# SCH_StairLights_2024-01-15.net
KiCad netlist of a schematic drawn in EasyEDA
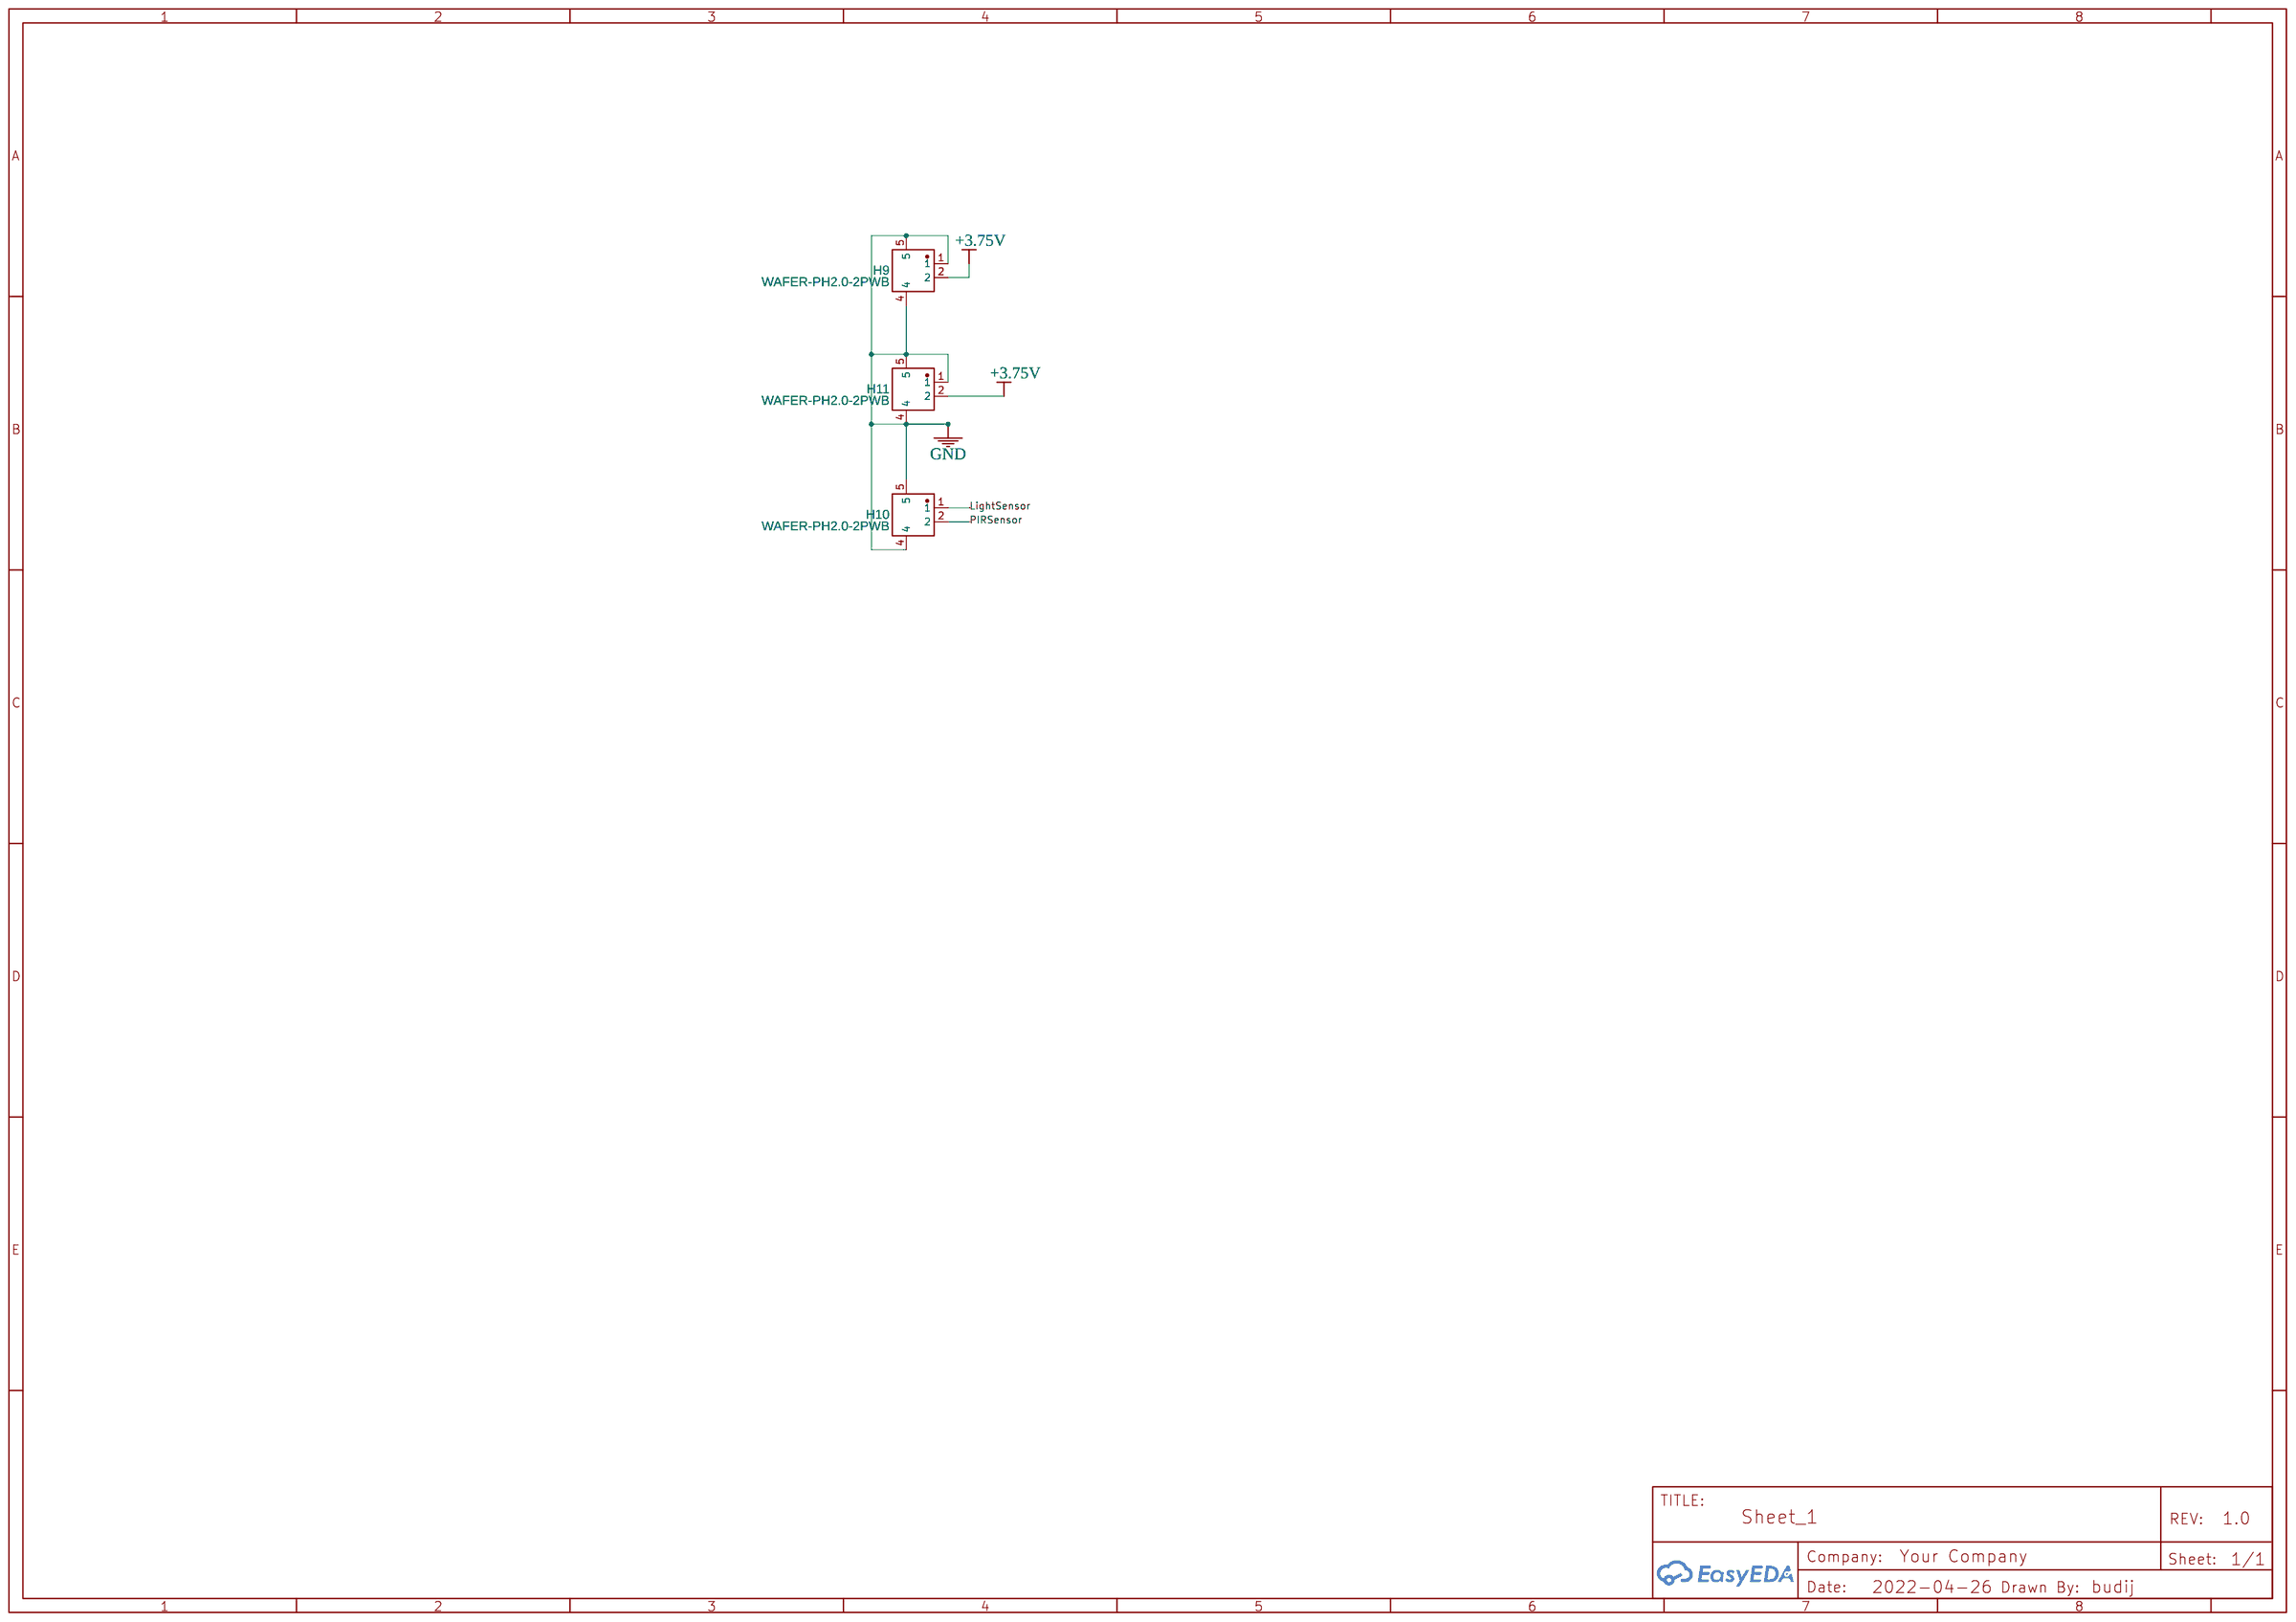
[diagram p0: StairLightsDigital]
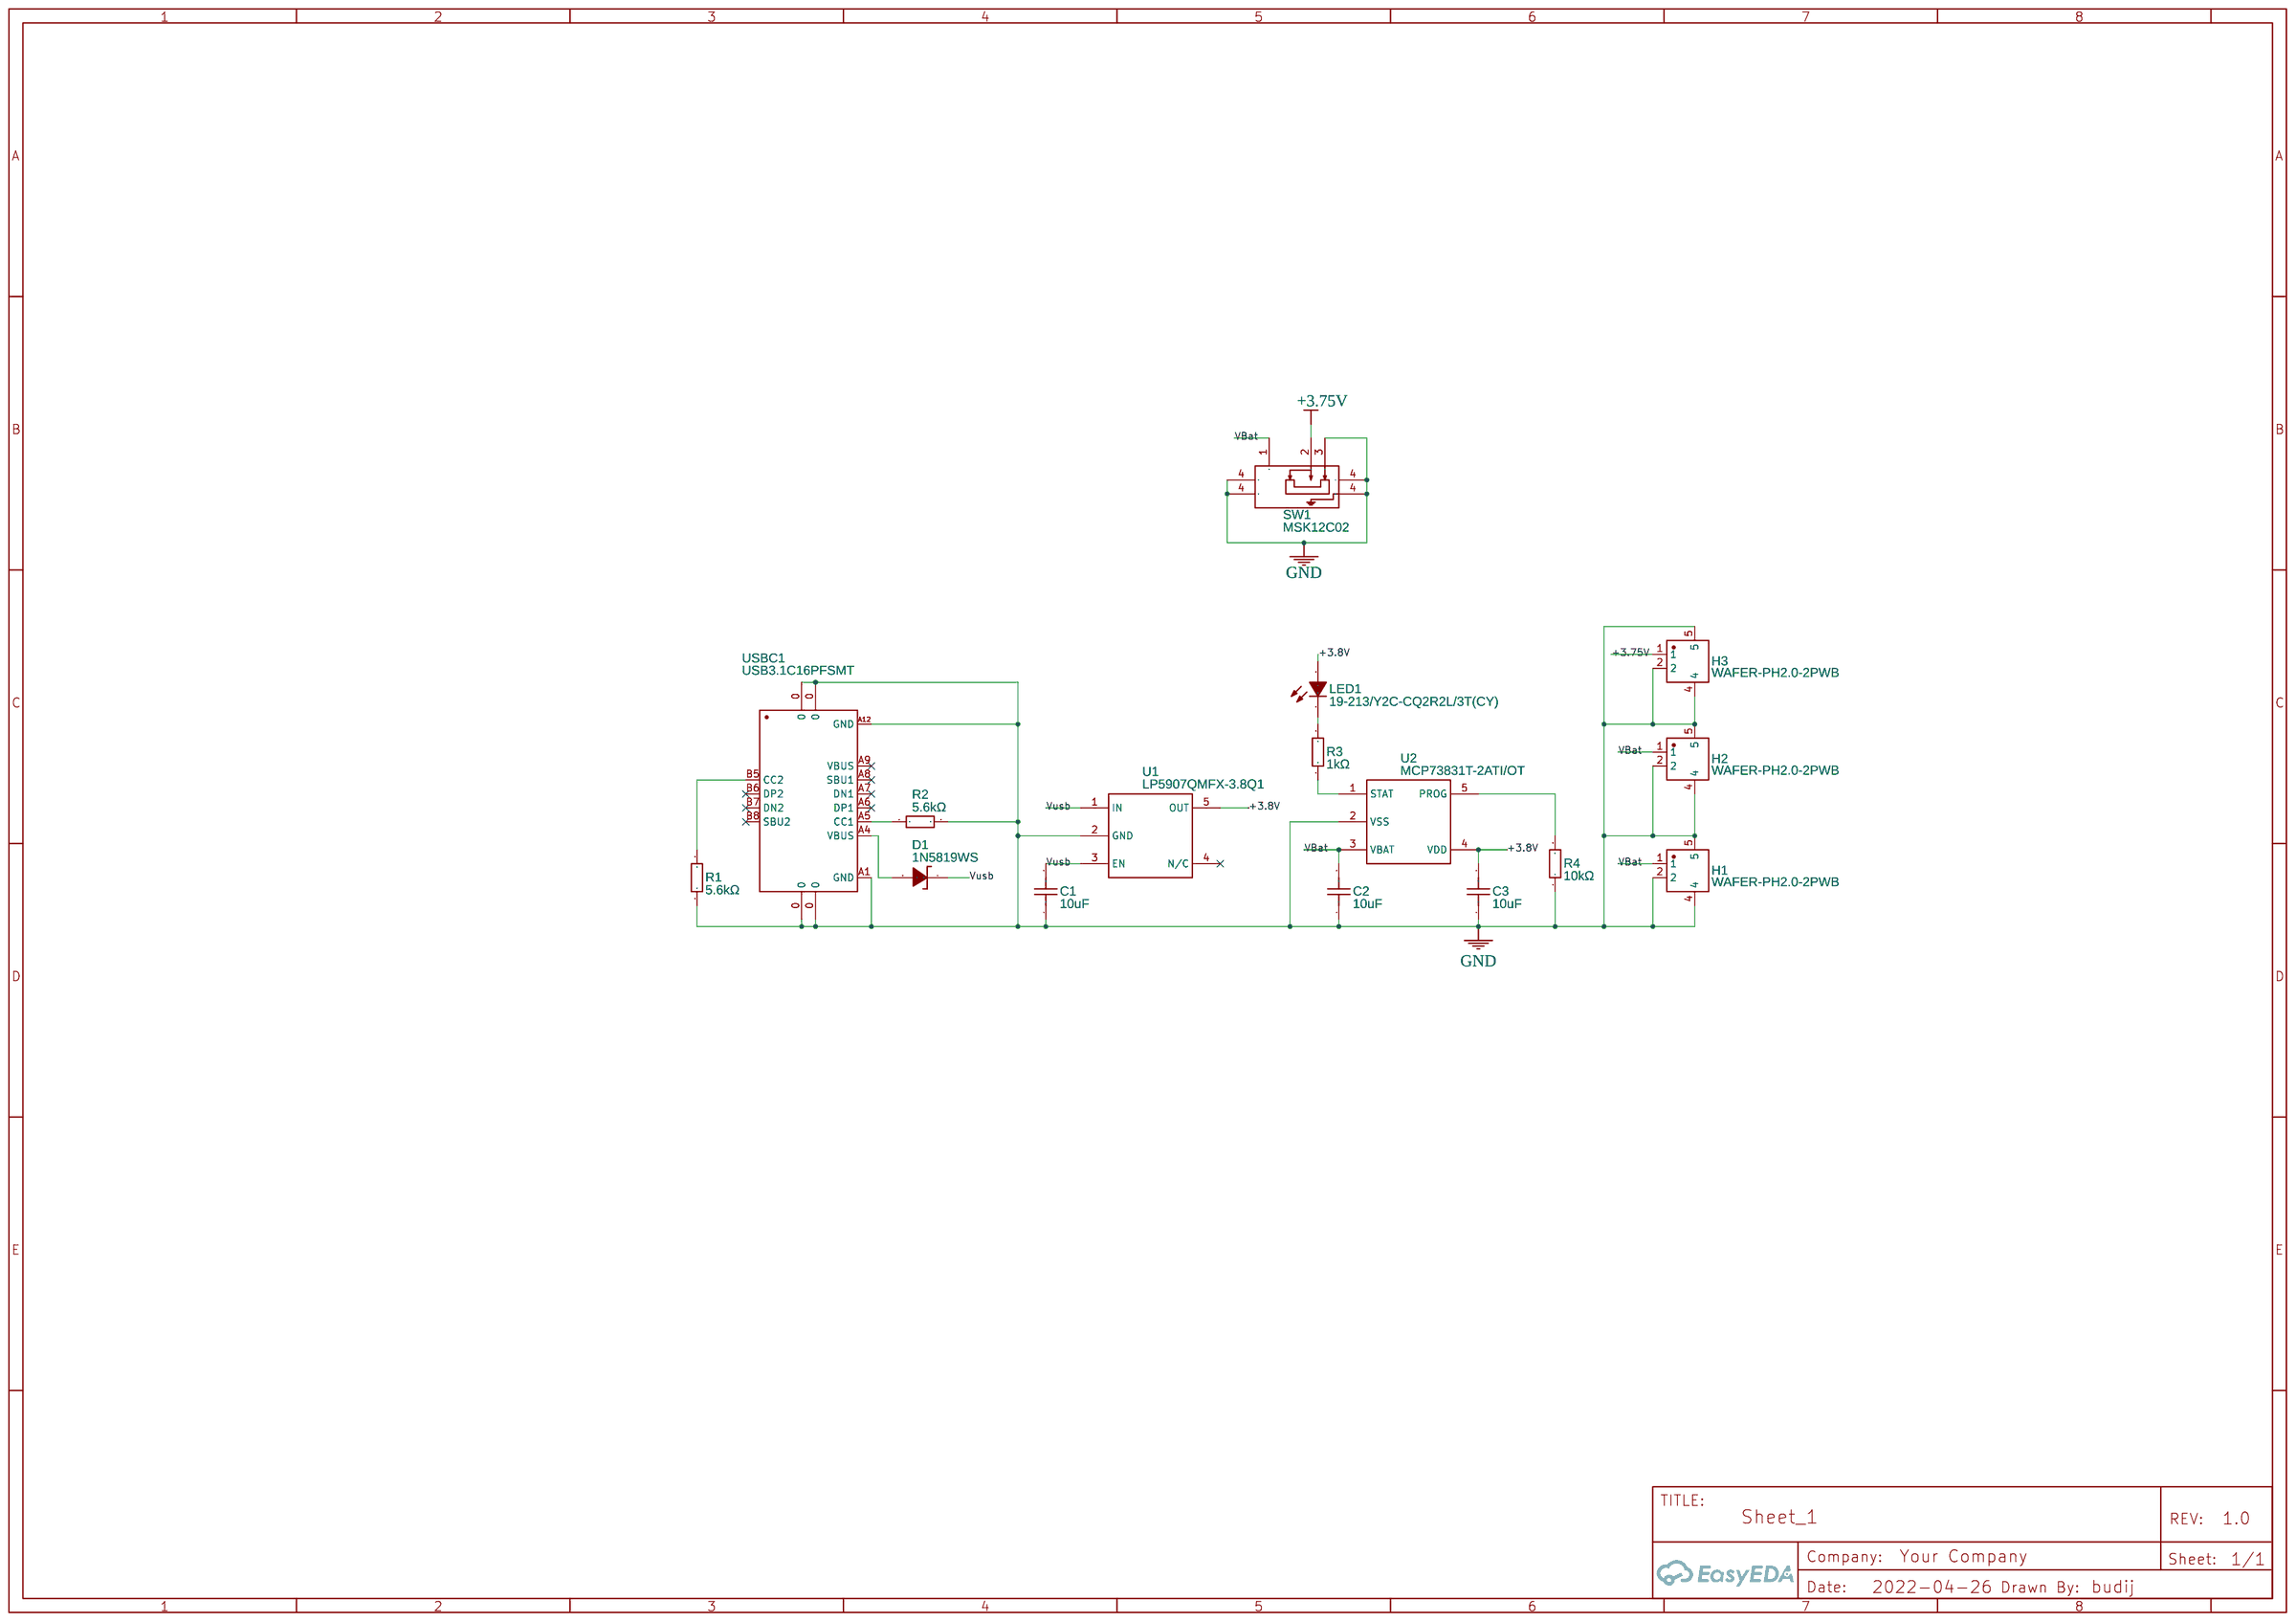
[diagram p1: PowerModule]
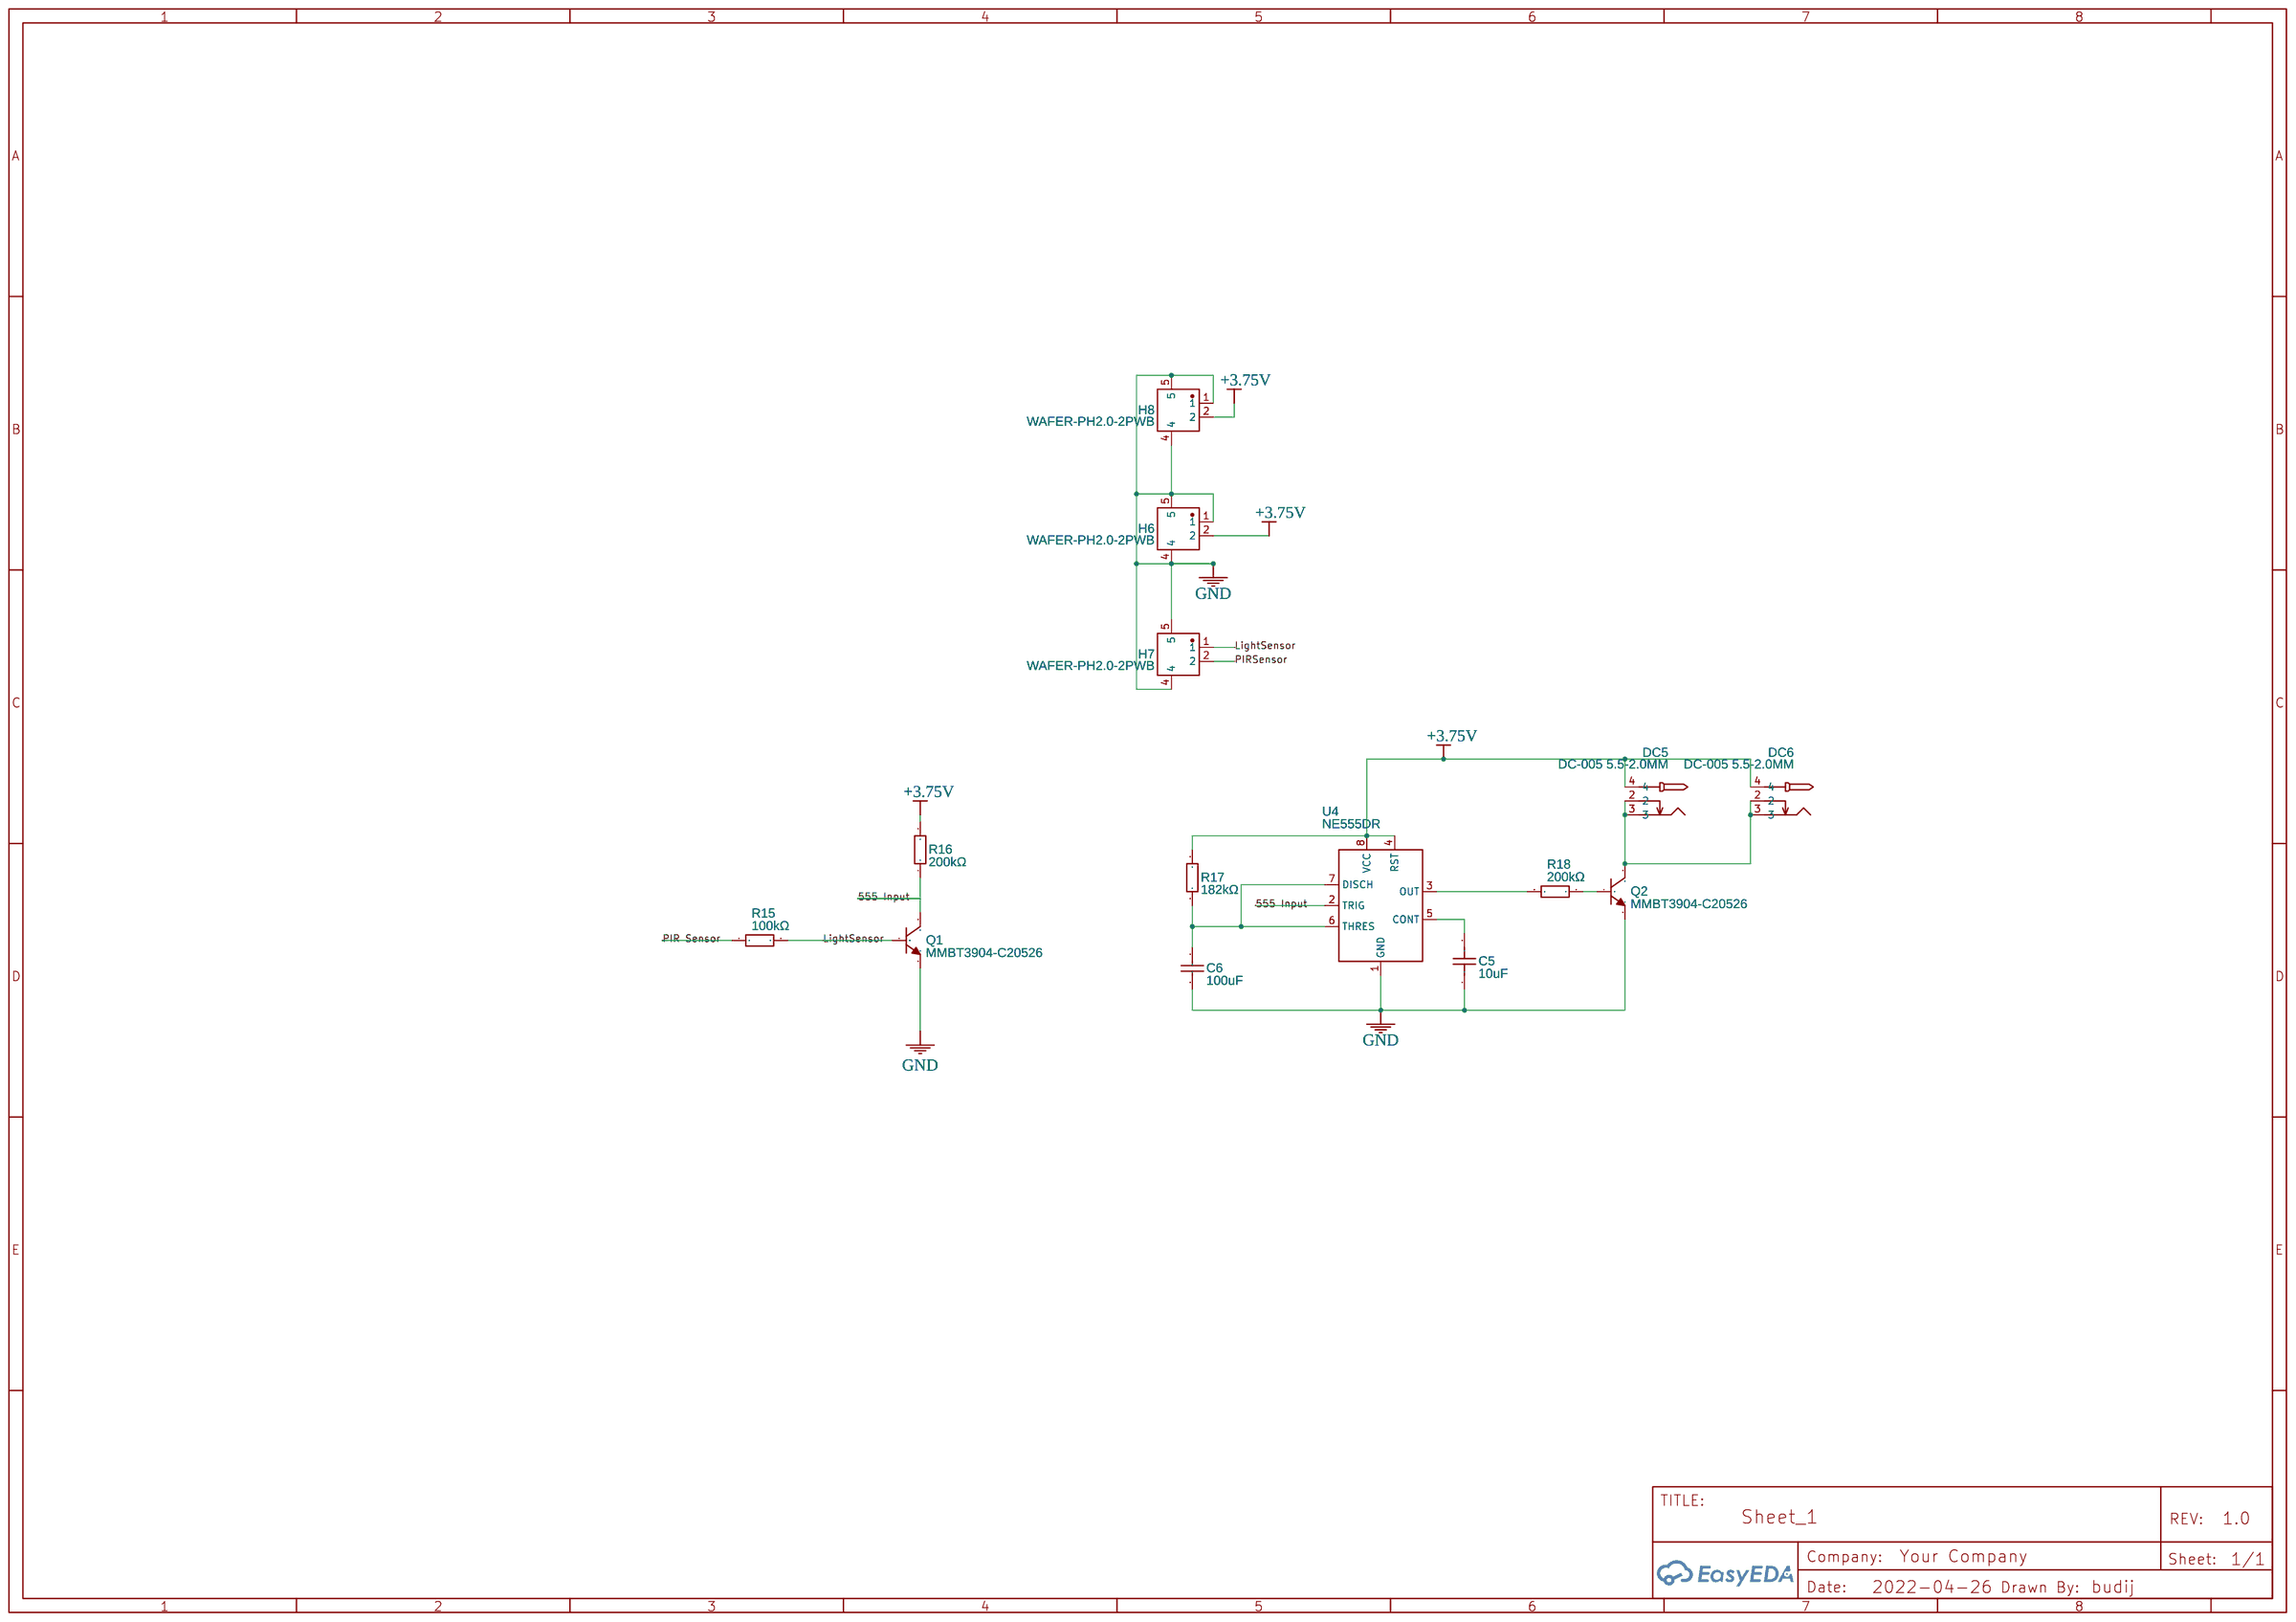
[diagram p2: StairLightsAnalog]
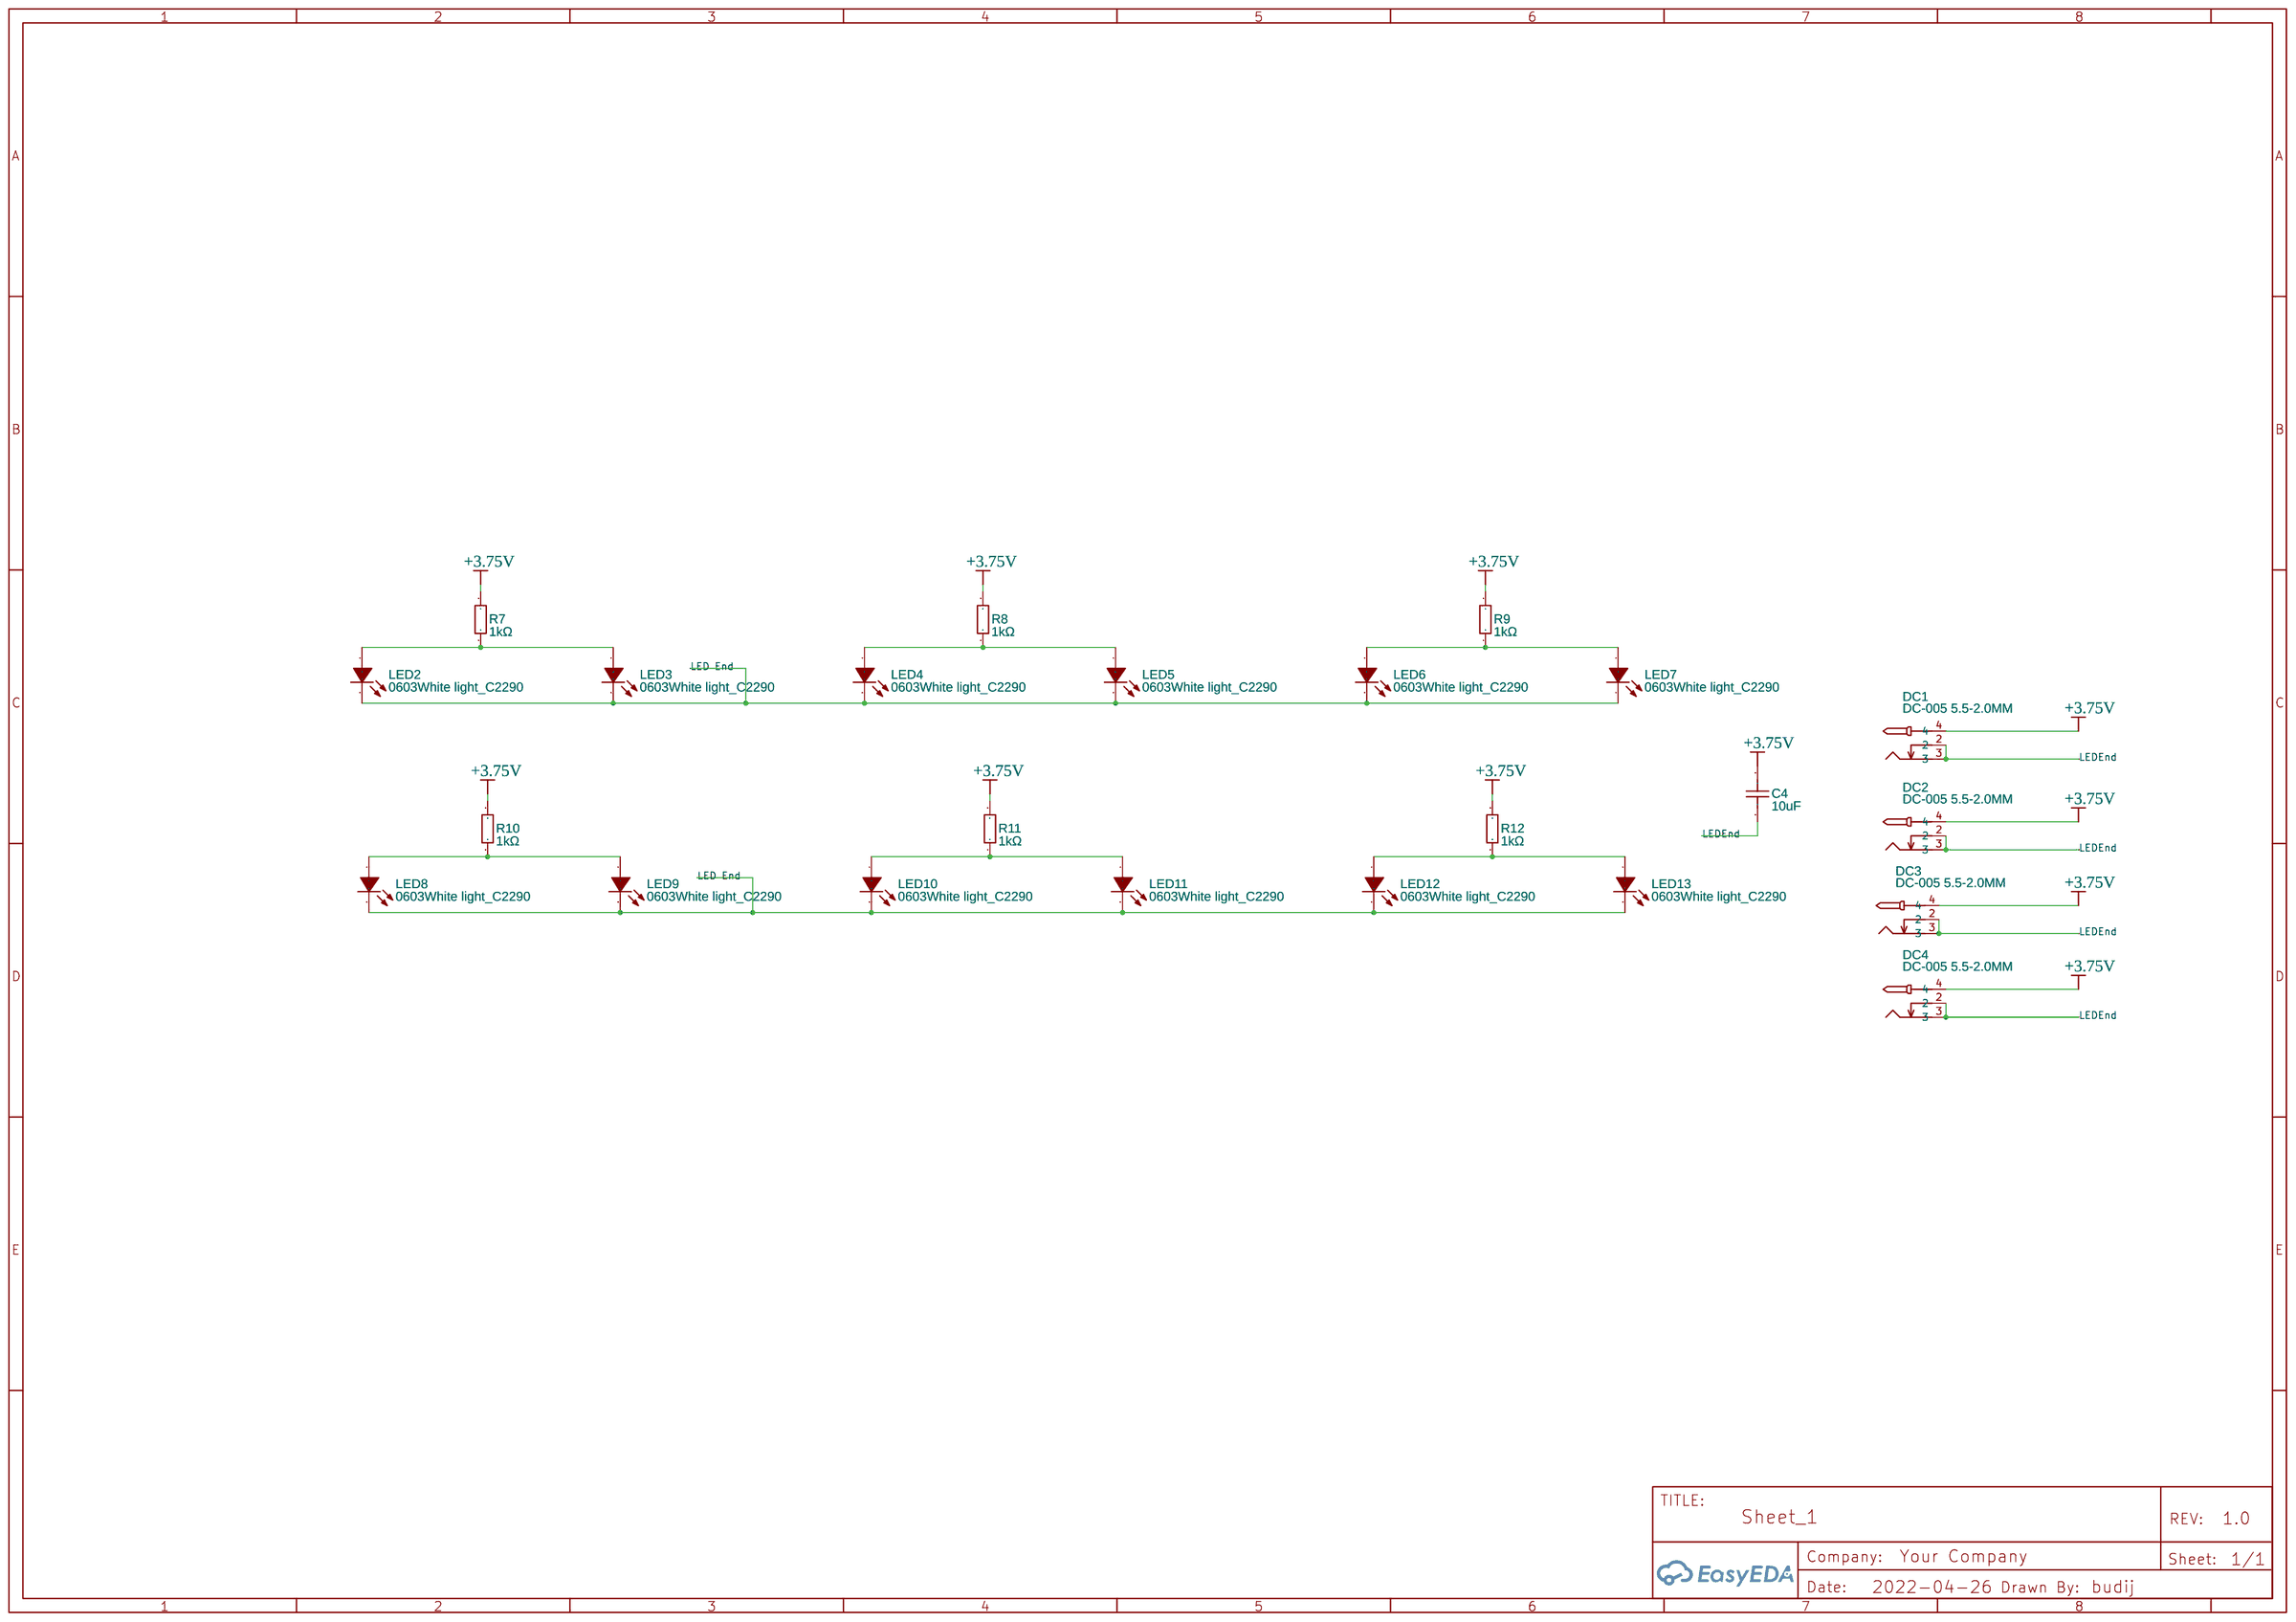
[diagram p3: LightsModule]
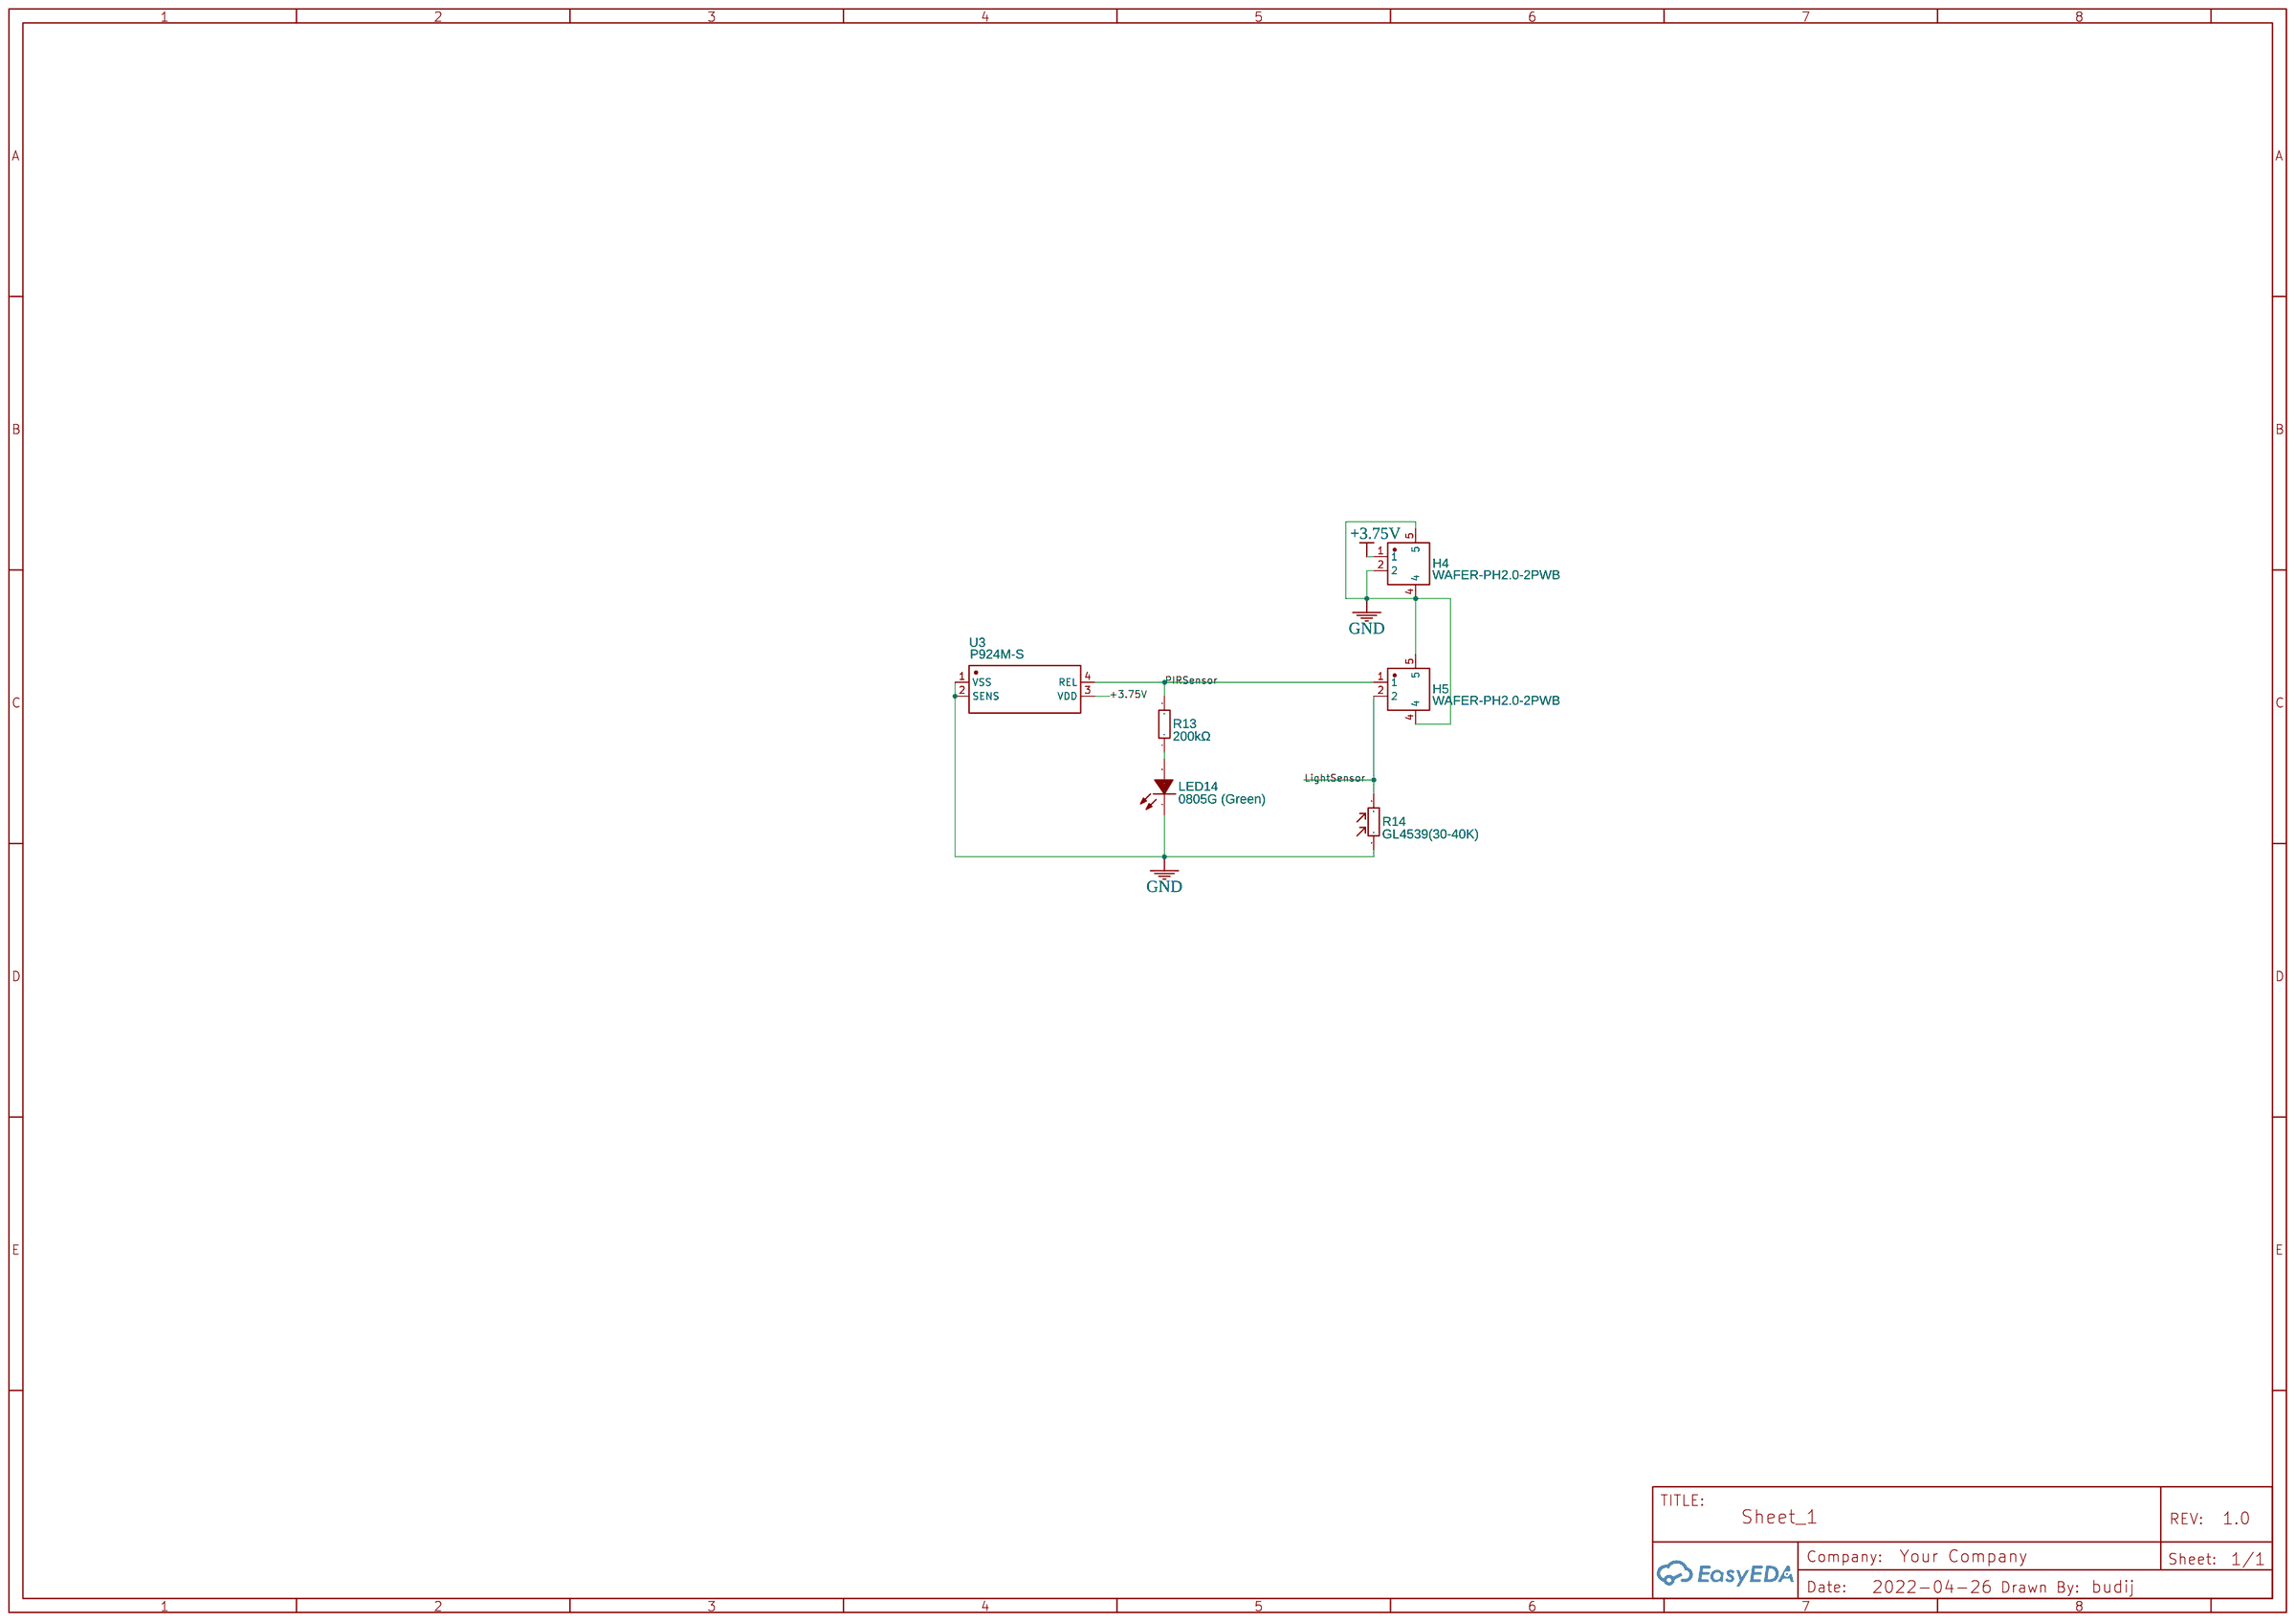
[diagram p4: SensorModule]

(export (version "E")
  (design (tool "Eeschema 10.0.6"))
  (components
    (comp (ref "H9")
      (value "WAFER-PH2.0-2PWB")
      (fields (field (name "Manufacturer") "XUNPU(讯普)"))
      (libsource (lib "") (part "WAFER-PH2.0-2PWB"))
    )
    (comp (ref "H10")
      (value "WAFER-PH2.0-2PWB")
      (fields (field (name "Manufacturer") "XUNPU(讯普)"))
      (libsource (lib "") (part "WAFER-PH2.0-2PWB"))
    )
    (comp (ref "H11")
      (value "WAFER-PH2.0-2PWB")
      (fields (field (name "Manufacturer") "XUNPU(讯普)"))
      (libsource (lib "") (part "WAFER-PH2.0-2PWB"))
    )
    (comp (ref "C1")
      (value "10uF")
      (fields
        (field (name "Manufacturer Part") "CL10A106KP8NNNC")
        (field (name "Manufacturer") "SAMSUNG(三星)")
      )
      (libsource (lib "") (part "CL10A106KP8NNNC"))
    )
    (comp (ref "C2")
      (value "10uF")
      (fields
        (field (name "Manufacturer Part") "CL10A106KP8NNNC")
        (field (name "Manufacturer") "SAMSUNG(三星)")
      )
      (libsource (lib "") (part "CL10A106KP8NNNC"))
    )
    (comp (ref "C3")
      (value "10uF")
      (fields
        (field (name "Manufacturer Part") "CL10A106KP8NNNC")
        (field (name "Manufacturer") "SAMSUNG(三星)")
      )
      (libsource (lib "") (part "CL10A106KP8NNNC"))
    )
    (comp (ref "D1")
      (value "1N5819WS")
      (fields (field (name "Manufacturer") "Hottech(合科泰)"))
      (libsource (lib "") (part "1N5819WS"))
    )
    (comp (ref "H1")
      (value "WAFER-PH2.0-2PWB")
      (fields (field (name "Manufacturer") "XUNPU(讯普)"))
      (libsource (lib "") (part "WAFER-PH2.0-2PWB"))
    )
    (comp (ref "H2")
      (value "WAFER-PH2.0-2PWB")
      (fields (field (name "Manufacturer") "XUNPU(讯普)"))
      (libsource (lib "") (part "WAFER-PH2.0-2PWB"))
    )
    (comp (ref "H3")
      (value "WAFER-PH2.0-2PWB")
      (fields (field (name "Manufacturer") "XUNPU(讯普)"))
      (libsource (lib "") (part "WAFER-PH2.0-2PWB"))
    )
    (comp (ref "LED1")
      (value "19-213/Y2C-CQ2R2L/3T(CY)")
      (fields (field (name "Manufacturer") "EVERLIGHT(亿光)"))
      (libsource (lib "") (part "19-213/Y2C-CQ2R2L/3T(CY)"))
    )
    (comp (ref "R1")
      (value "5.6kΩ")
      (fields
        (field (name "Manufacturer Part") "0603WAF5601T5E")
        (field (name "Manufacturer") "UNI-ROYAL(厚声)")
      )
      (libsource (lib "") (part "0603WAF5601T5E"))
    )
    (comp (ref "R2")
      (value "5.6kΩ")
      (fields
        (field (name "Manufacturer Part") "0603WAF5601T5E")
        (field (name "Manufacturer") "UNI-ROYAL(厚声)")
      )
      (libsource (lib "") (part "0603WAF5601T5E_1"))
    )
    (comp (ref "R3")
      (value "1kΩ")
      (fields
        (field (name "Manufacturer Part") "0603WAF1001T5E")
        (field (name "Manufacturer") "UNI-ROYAL(厚声)")
      )
      (libsource (lib "") (part "0603WAF1001T5E"))
    )
    (comp (ref "R4")
      (value "10kΩ")
      (fields
        (field (name "Manufacturer Part") "0603WAF1002T5E")
        (field (name "Manufacturer") "UNI-ROYAL(厚声)")
      )
      (libsource (lib "") (part "0603WAF1002T5E"))
    )
    (comp (ref "SW1")
      (value "MSK12C02")
      (fields (field (name "Manufacturer") "SHOU HAN(首韩)"))
      (libsource (lib "") (part "MSK12C02"))
    )
    (comp (ref "U1")
      (value "LP5907QMFX-3.8Q1")
      (fields (field (name "Manufacturer") "TI(德州仪器)"))
      (libsource (lib "") (part "LP5907QMFX-3.8Q1"))
    )
    (comp (ref "U2")
      (value "MCP73831T-2ATI/OT")
      (fields (field (name "Manufacturer") "MICROCHIP"))
      (libsource (lib "") (part "MCP73831T-2ATI/OT"))
    )
    (comp (ref "USBC1")
      (value "USB3.1C16PFSMT")
      (fields (field (name "Manufacturer") "LCSC"))
      (libsource (lib "") (part "USB3.1C16PFSMT"))
    )
    (comp (ref "C5")
      (value "10uF")
      (fields
        (field (name "Manufacturer Part") "CL10A106KP8NNNC")
        (field (name "Manufacturer") "SAMSUNG(三星)")
      )
      (libsource (lib "") (part "CL10A106KP8NNNC"))
    )
    (comp (ref "C6")
      (value "100uF")
      (fields
        (field (name "Manufacturer Part") "CL31A107MQHNNNE")
        (field (name "Manufacturer") "SAMSUNG(三星)")
      )
      (libsource (lib "") (part "CL31A107MQHNNNE"))
    )
    (comp (ref "DC5")
      (value "DC-005 5.5-2.0MM")
      (fields (field (name "Manufacturer Part") "DC-005 2.0") (field (name "Manufacturer") "BOOMELE(博穆精密)"))
      (libsource (lib "") (part "DC-005 5.5-2.0MM"))
    )
    (comp (ref "DC6")
      (value "DC-005 5.5-2.0MM")
      (fields (field (name "Manufacturer Part") "DC-005 2.0") (field (name "Manufacturer") "BOOMELE(博穆精密)"))
      (libsource (lib "") (part "DC-005 5.5-2.0MM"))
    )
    (comp (ref "H6")
      (value "WAFER-PH2.0-2PWB")
      (fields (field (name "Manufacturer") "XUNPU(讯普)"))
      (libsource (lib "") (part "WAFER-PH2.0-2PWB"))
    )
    (comp (ref "H7")
      (value "WAFER-PH2.0-2PWB")
      (fields (field (name "Manufacturer") "XUNPU(讯普)"))
      (libsource (lib "") (part "WAFER-PH2.0-2PWB"))
    )
    (comp (ref "H8")
      (value "WAFER-PH2.0-2PWB")
      (fields (field (name "Manufacturer") "XUNPU(讯普)"))
      (libsource (lib "") (part "WAFER-PH2.0-2PWB"))
    )
    (comp (ref "Q1")
      (value "MMBT3904-C20526")
      (fields (field (name "Manufacturer Part") "MMBT3904") (field (name "Manufacturer") "CJ(江苏长电/长晶)"))
      (libsource (lib "") (part "MMBT3904-C20526"))
    )
    (comp (ref "Q2")
      (value "MMBT3904-C20526")
      (fields (field (name "Manufacturer Part") "MMBT3904") (field (name "Manufacturer") "CJ(江苏长电/长晶)"))
      (libsource (lib "") (part "MMBT3904-C20526"))
    )
    (comp (ref "R15")
      (value "100kΩ")
      (fields
        (field (name "Manufacturer Part") "0603WAF1003T5E")
        (field (name "Manufacturer") "UNI-ROYAL(厚声)")
      )
      (libsource (lib "") (part "0603WAF1003T5E"))
    )
    (comp (ref "R16")
      (value "200kΩ")
      (fields
        (field (name "Manufacturer Part") "0603WAF2003T5E")
        (field (name "Manufacturer") "UNI-ROYAL(厚声)")
      )
      (libsource (lib "") (part "0603WAF2003T5E_1"))
    )
    (comp (ref "R17")
      (value "182kΩ")
      (fields (field (name "Manufacturer Part") "CR0603-FX-1823ELF") (field (name "Manufacturer") "BOURNS"))
      (libsource (lib "") (part "CR0603-FX-1823ELF"))
    )
    (comp (ref "R18")
      (value "200kΩ")
      (fields
        (field (name "Manufacturer Part") "0603WAF2003T5E")
        (field (name "Manufacturer") "UNI-ROYAL(厚声)")
      )
      (libsource (lib "") (part "0603WAF2003T5E"))
    )
    (comp (ref "U4")
      (value "NE555DR")
      (fields (field (name "Manufacturer") "TI"))
      (libsource (lib "") (part "NE555DR"))
    )
    (comp (ref "C4")
      (value "10uF")
      (fields
        (field (name "Manufacturer Part") "CL10A106KP8NNNC")
        (field (name "Manufacturer") "SAMSUNG(三星)")
      )
      (libsource (lib "") (part "CL10A106KP8NNNC"))
    )
    (comp (ref "DC1")
      (value "DC-005 5.5-2.0MM")
      (fields (field (name "Manufacturer Part") "DC-005 2.0") (field (name "Manufacturer") "BOOMELE(博穆精密)"))
      (libsource (lib "") (part "DC-005 5.5-2.0MM"))
    )
    (comp (ref "DC2")
      (value "DC-005 5.5-2.0MM")
      (fields (field (name "Manufacturer Part") "DC-005 2.0") (field (name "Manufacturer") "BOOMELE(博穆精密)"))
      (libsource (lib "") (part "DC-005 5.5-2.0MM"))
    )
    (comp (ref "DC3")
      (value "DC-005 5.5-2.0MM")
      (fields (field (name "Manufacturer Part") "DC-005 2.0") (field (name "Manufacturer") "BOOMELE(博穆精密)"))
      (libsource (lib "") (part "DC-005 5.5-2.0MM"))
    )
    (comp (ref "DC4")
      (value "DC-005 5.5-2.0MM")
      (fields (field (name "Manufacturer Part") "DC-005 2.0") (field (name "Manufacturer") "BOOMELE(博穆精密)"))
      (libsource (lib "") (part "DC-005 5.5-2.0MM"))
    )
    (comp (ref "LED2")
      (value "0603White light_C2290")
      (fields (field (name "Manufacturer Part") "KT-0603白灯"))
      (libsource (lib "") (part "0603White light_C2290"))
    )
    (comp (ref "LED3")
      (value "0603White light_C2290")
      (fields (field (name "Manufacturer Part") "KT-0603白灯"))
      (libsource (lib "") (part "0603White light_C2290"))
    )
    (comp (ref "LED4")
      (value "0603White light_C2290")
      (fields (field (name "Manufacturer Part") "KT-0603白灯"))
      (libsource (lib "") (part "0603White light_C2290"))
    )
    (comp (ref "LED5")
      (value "0603White light_C2290")
      (fields (field (name "Manufacturer Part") "KT-0603白灯"))
      (libsource (lib "") (part "0603White light_C2290"))
    )
    (comp (ref "LED6")
      (value "0603White light_C2290")
      (fields (field (name "Manufacturer Part") "KT-0603白灯"))
      (libsource (lib "") (part "0603White light_C2290"))
    )
    (comp (ref "LED7")
      (value "0603White light_C2290")
      (fields (field (name "Manufacturer Part") "KT-0603白灯"))
      (libsource (lib "") (part "0603White light_C2290"))
    )
    (comp (ref "LED8")
      (value "0603White light_C2290")
      (fields (field (name "Manufacturer Part") "KT-0603白灯"))
      (libsource (lib "") (part "0603White light_C2290"))
    )
    (comp (ref "LED9")
      (value "0603White light_C2290")
      (fields (field (name "Manufacturer Part") "KT-0603白灯"))
      (libsource (lib "") (part "0603White light_C2290"))
    )
    (comp (ref "LED10")
      (value "0603White light_C2290")
      (fields (field (name "Manufacturer Part") "KT-0603白灯"))
      (libsource (lib "") (part "0603White light_C2290"))
    )
    (comp (ref "LED11")
      (value "0603White light_C2290")
      (fields (field (name "Manufacturer Part") "KT-0603白灯"))
      (libsource (lib "") (part "0603White light_C2290"))
    )
    (comp (ref "LED12")
      (value "0603White light_C2290")
      (fields (field (name "Manufacturer Part") "KT-0603白灯"))
      (libsource (lib "") (part "0603White light_C2290"))
    )
    (comp (ref "LED13")
      (value "0603White light_C2290")
      (fields (field (name "Manufacturer Part") "KT-0603白灯"))
      (libsource (lib "") (part "0603White light_C2290"))
    )
    (comp (ref "R7")
      (value "1kΩ")
      (fields
        (field (name "Manufacturer Part") "0603WAF1001T5E")
        (field (name "Manufacturer") "UNI-ROYAL(厚声)")
      )
      (libsource (lib "") (part "0603WAF1001T5E"))
    )
    (comp (ref "R8")
      (value "1kΩ")
      (fields
        (field (name "Manufacturer Part") "0603WAF1001T5E")
        (field (name "Manufacturer") "UNI-ROYAL(厚声)")
      )
      (libsource (lib "") (part "0603WAF1001T5E"))
    )
    (comp (ref "R9")
      (value "1kΩ")
      (fields
        (field (name "Manufacturer Part") "0603WAF1001T5E")
        (field (name "Manufacturer") "UNI-ROYAL(厚声)")
      )
      (libsource (lib "") (part "0603WAF1001T5E"))
    )
    (comp (ref "R10")
      (value "1kΩ")
      (fields
        (field (name "Manufacturer Part") "0603WAF1001T5E")
        (field (name "Manufacturer") "UNI-ROYAL(厚声)")
      )
      (libsource (lib "") (part "0603WAF1001T5E"))
    )
    (comp (ref "R11")
      (value "1kΩ")
      (fields
        (field (name "Manufacturer Part") "0603WAF1001T5E")
        (field (name "Manufacturer") "UNI-ROYAL(厚声)")
      )
      (libsource (lib "") (part "0603WAF1001T5E"))
    )
    (comp (ref "R12")
      (value "1kΩ")
      (fields
        (field (name "Manufacturer Part") "0603WAF1001T5E")
        (field (name "Manufacturer") "UNI-ROYAL(厚声)")
      )
      (libsource (lib "") (part "0603WAF1001T5E"))
    )
    (comp (ref "H4")
      (value "WAFER-PH2.0-2PWB")
      (fields (field (name "Manufacturer") "XUNPU(讯普)"))
      (libsource (lib "") (part "WAFER-PH2.0-2PWB"))
    )
    (comp (ref "H5")
      (value "WAFER-PH2.0-2PWB")
      (fields (field (name "Manufacturer") "XUNPU(讯普)"))
      (libsource (lib "") (part "WAFER-PH2.0-2PWB"))
    )
    (comp (ref "LED14")
      (value "0805G (Green)")
      (fields (field (name "Manufacturer") "KENTO"))
      (libsource (lib "") (part "0805G (Green)"))
    )
    (comp (ref "R13")
      (value "200kΩ")
      (fields
        (field (name "Manufacturer Part") "0603WAF1002T5E")
        (field (name "Manufacturer") "UNI-ROYAL(厚声)")
      )
      (libsource (lib "") (part "0603WAF1002T5E"))
    )
    (comp (ref "R14")
      (value "GL4539(30-40K)")
      (fields (field (name "Manufacturer") "ReliaPro"))
      (libsource (lib "") (part "GL4539(30-40K)"))
    )
    (comp (ref "U3")
      (value "P924M-S")
      (fields (field (name "Manufacturer") "Nicera"))
      (libsource (lib "") (part "P924M-S"))
    )
  )
  (nets
    (net (code "1") (name "+3.8V") (class "Default")
      (node (ref "C3") (pin "2") (pinfunction "2_2") (pintype "unspecified"))
      (node (ref "LED1") (pin "2") (pinfunction "A_2") (pintype "input"))
      (node (ref "U1") (pin "5") (pinfunction "OUT_5") (pintype "unspecified"))
      (node (ref "U2") (pin "4") (pinfunction "VDD_4") (pintype "unspecified"))
    )
    (net (code "2") (name "+3.75V") (class "Default")
      (node (ref "C4") (pin "2") (pinfunction "2_2") (pintype "unspecified"))
      (node (ref "DC1") (pin "4") (pinfunction "4_4") (pintype "unspecified"))
      (node (ref "DC2") (pin "4") (pinfunction "4_4") (pintype "unspecified"))
      (node (ref "DC3") (pin "4") (pinfunction "4_4") (pintype "unspecified"))
      (node (ref "DC4") (pin "4") (pinfunction "4_4") (pintype "unspecified"))
      (node (ref "DC5") (pin "4") (pinfunction "4_4") (pintype "unspecified"))
      (node (ref "DC6") (pin "4") (pinfunction "4_4") (pintype "unspecified"))
      (node (ref "H11") (pin "2") (pinfunction "2_2") (pintype "unspecified"))
      (node (ref "H3") (pin "1") (pinfunction "1_1") (pintype "unspecified"))
      (node (ref "H4") (pin "1") (pinfunction "1_1") (pintype "unspecified"))
      (node (ref "H6") (pin "2") (pinfunction "2_2") (pintype "unspecified"))
      (node (ref "H8") (pin "2") (pinfunction "2_2") (pintype "unspecified"))
      (node (ref "H9") (pin "2") (pinfunction "2_2") (pintype "unspecified"))
      (node (ref "R10") (pin "2") (pinfunction "2_2") (pintype "input"))
      (node (ref "R11") (pin "2") (pinfunction "2_2") (pintype "input"))
      (node (ref "R12") (pin "2") (pinfunction "2_2") (pintype "input"))
      (node (ref "R16") (pin "2") (pinfunction "2_2") (pintype "input"))
      (node (ref "R17") (pin "1") (pinfunction "1_1") (pintype "unspecified"))
      (node (ref "R7") (pin "2") (pinfunction "2_2") (pintype "input"))
      (node (ref "R8") (pin "2") (pinfunction "2_2") (pintype "input"))
      (node (ref "R9") (pin "2") (pinfunction "2_2") (pintype "input"))
      (node (ref "SW1") (pin "2") (pinfunction "2_2") (pintype "unspecified"))
      (node (ref "U3") (pin "3") (pinfunction "VDD_3") (pintype "unspecified"))
      (node (ref "U4") (pin "4") (pinfunction "RST_4") (pintype "unspecified"))
      (node (ref "U4") (pin "8") (pinfunction "VCC_8") (pintype "unspecified"))
    )
    (net (code "3") (name "555 Input") (class "Default")
      (node (ref "Q1") (pin "3") (pinfunction "C_3") (pintype "unspecified"))
      (node (ref "R16") (pin "1") (pinfunction "1_1") (pintype "input"))
      (node (ref "U4") (pin "2") (pinfunction "TRIG_2") (pintype "unspecified"))
    )
    (net (code "4") (name "GND") (class "Default")
      (node (ref "C1") (pin "1") (pinfunction "1_1") (pintype "unspecified"))
      (node (ref "C2") (pin "1") (pinfunction "1_1") (pintype "unspecified"))
      (node (ref "C3") (pin "1") (pinfunction "1_1") (pintype "unspecified"))
      (node (ref "C5") (pin "1") (pinfunction "1_1") (pintype "unspecified"))
      (node (ref "C6") (pin "1") (pinfunction "1_1") (pintype "input"))
      (node (ref "H1") (pin "2") (pinfunction "2_2") (pintype "unspecified"))
      (node (ref "H1") (pin "4") (pinfunction "4_4") (pintype "unspecified"))
      (node (ref "H1") (pin "5") (pinfunction "5_5") (pintype "unspecified"))
      (node (ref "H10") (pin "4") (pinfunction "4_4") (pintype "unspecified"))
      (node (ref "H10") (pin "5") (pinfunction "5_5") (pintype "unspecified"))
      (node (ref "H11") (pin "1") (pinfunction "1_1") (pintype "unspecified"))
      (node (ref "H11") (pin "4") (pinfunction "4_4") (pintype "unspecified"))
      (node (ref "H11") (pin "5") (pinfunction "5_5") (pintype "unspecified"))
      (node (ref "H2") (pin "2") (pinfunction "2_2") (pintype "unspecified"))
      (node (ref "H2") (pin "4") (pinfunction "4_4") (pintype "unspecified"))
      (node (ref "H2") (pin "5") (pinfunction "5_5") (pintype "unspecified"))
      (node (ref "H3") (pin "2") (pinfunction "2_2") (pintype "unspecified"))
      (node (ref "H3") (pin "4") (pinfunction "4_4") (pintype "unspecified"))
      (node (ref "H3") (pin "5") (pinfunction "5_5") (pintype "unspecified"))
      (node (ref "H4") (pin "2") (pinfunction "2_2") (pintype "unspecified"))
      (node (ref "H4") (pin "4") (pinfunction "4_4") (pintype "unspecified"))
      (node (ref "H4") (pin "5") (pinfunction "5_5") (pintype "unspecified"))
      (node (ref "H5") (pin "4") (pinfunction "4_4") (pintype "unspecified"))
      (node (ref "H5") (pin "5") (pinfunction "5_5") (pintype "unspecified"))
      (node (ref "H6") (pin "1") (pinfunction "1_1") (pintype "unspecified"))
      (node (ref "H6") (pin "4") (pinfunction "4_4") (pintype "unspecified"))
      (node (ref "H6") (pin "5") (pinfunction "5_5") (pintype "unspecified"))
      (node (ref "H7") (pin "4") (pinfunction "4_4") (pintype "unspecified"))
      (node (ref "H7") (pin "5") (pinfunction "5_5") (pintype "unspecified"))
      (node (ref "H8") (pin "1") (pinfunction "1_1") (pintype "unspecified"))
      (node (ref "H8") (pin "4") (pinfunction "4_4") (pintype "unspecified"))
      (node (ref "H8") (pin "5") (pinfunction "5_5") (pintype "unspecified"))
      (node (ref "H9") (pin "1") (pinfunction "1_1") (pintype "unspecified"))
      (node (ref "H9") (pin "4") (pinfunction "4_4") (pintype "unspecified"))
      (node (ref "H9") (pin "5") (pinfunction "5_5") (pintype "unspecified"))
      (node (ref "LED14") (pin "1") (pinfunction "K_1") (pintype "unspecified"))
      (node (ref "Q1") (pin "2") (pinfunction "E_2") (pintype "unspecified"))
      (node (ref "Q2") (pin "2") (pinfunction "E_2") (pintype "unspecified"))
      (node (ref "R1") (pin "1") (pinfunction "1_1") (pintype "input"))
      (node (ref "R14") (pin "1") (pinfunction "1_1") (pintype "input"))
      (node (ref "R2") (pin "2") (pinfunction "2_2") (pintype "input"))
      (node (ref "R4") (pin "1") (pinfunction "1_1") (pintype "input"))
      (node (ref "SW1") (pin "3") (pinfunction "3_3") (pintype "unspecified"))
      (node (ref "SW1") (pin "4") (pinfunction "4_4") (pintype "unspecified"))
      (node (ref "U1") (pin "2") (pinfunction "GND_2") (pintype "unspecified"))
      (node (ref "U2") (pin "2") (pinfunction "VSS_2") (pintype "unspecified"))
      (node (ref "U3") (pin "1") (pinfunction "VSS_1") (pintype "unspecified"))
      (node (ref "U3") (pin "2") (pinfunction "SENS_2") (pintype "unspecified"))
      (node (ref "U4") (pin "1") (pinfunction "GND_1") (pintype "unspecified"))
      (node (ref "USBC1") (pin "0") (pinfunction "0_0") (pintype "unspecified"))
      (node (ref "USBC1") (pin "A1") (pinfunction "GND_A1") (pintype "unspecified"))
      (node (ref "USBC1") (pin "A12") (pinfunction "GND_A12") (pintype "unspecified"))
    )
    (net (code "5") (name "LED End") (class "Default")
      (node (ref "LED10") (pin "2") (pinfunction "K_2") (pintype "unspecified"))
      (node (ref "LED11") (pin "2") (pinfunction "K_2") (pintype "unspecified"))
      (node (ref "LED12") (pin "2") (pinfunction "K_2") (pintype "unspecified"))
      (node (ref "LED13") (pin "2") (pinfunction "K_2") (pintype "unspecified"))
      (node (ref "LED2") (pin "2") (pinfunction "K_2") (pintype "unspecified"))
      (node (ref "LED3") (pin "2") (pinfunction "K_2") (pintype "unspecified"))
      (node (ref "LED4") (pin "2") (pinfunction "K_2") (pintype "unspecified"))
      (node (ref "LED5") (pin "2") (pinfunction "K_2") (pintype "unspecified"))
      (node (ref "LED6") (pin "2") (pinfunction "K_2") (pintype "unspecified"))
      (node (ref "LED7") (pin "2") (pinfunction "K_2") (pintype "unspecified"))
      (node (ref "LED8") (pin "2") (pinfunction "K_2") (pintype "unspecified"))
      (node (ref "LED9") (pin "2") (pinfunction "K_2") (pintype "unspecified"))
    )
    (net (code "6") (name "LEDEnd") (class "Default")
      (node (ref "C4") (pin "1") (pinfunction "1_1") (pintype "unspecified"))
      (node (ref "DC1") (pin "2") (pinfunction "2_2") (pintype "unspecified"))
      (node (ref "DC1") (pin "3") (pinfunction "3_3") (pintype "unspecified"))
      (node (ref "DC2") (pin "2") (pinfunction "2_2") (pintype "unspecified"))
      (node (ref "DC2") (pin "3") (pinfunction "3_3") (pintype "unspecified"))
      (node (ref "DC3") (pin "2") (pinfunction "2_2") (pintype "unspecified"))
      (node (ref "DC3") (pin "3") (pinfunction "3_3") (pintype "unspecified"))
      (node (ref "DC4") (pin "2") (pinfunction "2_2") (pintype "unspecified"))
      (node (ref "DC4") (pin "3") (pinfunction "3_3") (pintype "unspecified"))
    )
    (net (code "7") (name "LightSensor") (class "Default")
      (node (ref "H10") (pin "1") (pinfunction "1_1") (pintype "unspecified"))
      (node (ref "H5") (pin "2") (pinfunction "2_2") (pintype "unspecified"))
      (node (ref "H7") (pin "1") (pinfunction "1_1") (pintype "unspecified"))
      (node (ref "Q1") (pin "1") (pinfunction "B_1") (pintype "unspecified"))
      (node (ref "R14") (pin "2") (pinfunction "2_2") (pintype "input"))
      (node (ref "R15") (pin "2") (pinfunction "2_2") (pintype "input"))
    )
    (net (code "8") (name "Net-(D1-A)") (class "Default")
      (node (ref "D1") (pin "2") (pinfunction "A_2") (pintype "unspecified"))
      (node (ref "USBC1") (pin "A4") (pinfunction "VBUS_A4") (pintype "unspecified"))
    )
    (net (code "9") (name "Net-(LED1-C)") (class "Default")
      (node (ref "LED1") (pin "1") (pinfunction "C_1") (pintype "input"))
      (node (ref "R3") (pin "2") (pinfunction "2_2") (pintype "input"))
    )
    (net (code "10") (name "Net-(LED2-A)") (class "Default")
      (node (ref "LED2") (pin "1") (pinfunction "A_1") (pintype "unspecified"))
      (node (ref "LED3") (pin "1") (pinfunction "A_1") (pintype "unspecified"))
      (node (ref "R7") (pin "1") (pinfunction "1_1") (pintype "input"))
    )
    (net (code "11") (name "Net-(LED4-A)") (class "Default")
      (node (ref "LED4") (pin "1") (pinfunction "A_1") (pintype "unspecified"))
      (node (ref "LED5") (pin "1") (pinfunction "A_1") (pintype "unspecified"))
      (node (ref "R8") (pin "1") (pinfunction "1_1") (pintype "input"))
    )
    (net (code "12") (name "Net-(LED6-A)") (class "Default")
      (node (ref "LED6") (pin "1") (pinfunction "A_1") (pintype "unspecified"))
      (node (ref "LED7") (pin "1") (pinfunction "A_1") (pintype "unspecified"))
      (node (ref "R9") (pin "1") (pinfunction "1_1") (pintype "input"))
    )
    (net (code "13") (name "Net-(LED8-A)") (class "Default")
      (node (ref "LED8") (pin "1") (pinfunction "A_1") (pintype "unspecified"))
      (node (ref "LED9") (pin "1") (pinfunction "A_1") (pintype "unspecified"))
      (node (ref "R10") (pin "1") (pinfunction "1_1") (pintype "input"))
    )
    (net (code "14") (name "Net-(LED10-A)") (class "Default")
      (node (ref "LED10") (pin "1") (pinfunction "A_1") (pintype "unspecified"))
      (node (ref "LED11") (pin "1") (pinfunction "A_1") (pintype "unspecified"))
      (node (ref "R11") (pin "1") (pinfunction "1_1") (pintype "input"))
    )
    (net (code "15") (name "Net-(LED12-A)") (class "Default")
      (node (ref "LED12") (pin "1") (pinfunction "A_1") (pintype "unspecified"))
      (node (ref "LED13") (pin "1") (pinfunction "A_1") (pintype "unspecified"))
      (node (ref "R12") (pin "1") (pinfunction "1_1") (pintype "input"))
    )
    (net (code "16") (name "Net-(LED14-A)") (class "Default")
      (node (ref "LED14") (pin "2") (pinfunction "A_2") (pintype "unspecified"))
      (node (ref "R13") (pin "1") (pinfunction "1_1") (pintype "input"))
    )
    (net (code "17") (name "Net-(Q2-B)") (class "Default")
      (node (ref "Q2") (pin "1") (pinfunction "B_1") (pintype "unspecified"))
      (node (ref "R18") (pin "1") (pinfunction "1_1") (pintype "input"))
    )
    (net (code "18") (name "Net-(Q2-C)") (class "Default")
      (node (ref "DC5") (pin "2") (pinfunction "2_2") (pintype "unspecified"))
      (node (ref "DC5") (pin "3") (pinfunction "3_3") (pintype "unspecified"))
      (node (ref "DC6") (pin "2") (pinfunction "2_2") (pintype "unspecified"))
      (node (ref "DC6") (pin "3") (pinfunction "3_3") (pintype "unspecified"))
      (node (ref "Q2") (pin "3") (pinfunction "C_3") (pintype "unspecified"))
    )
    (net (code "19") (name "Net-(U2-PROG)") (class "Default")
      (node (ref "R4") (pin "2") (pinfunction "2_2") (pintype "input"))
      (node (ref "U2") (pin "5") (pinfunction "PROG_5") (pintype "unspecified"))
    )
    (net (code "20") (name "Net-(U2-STAT)") (class "Default")
      (node (ref "R3") (pin "1") (pinfunction "1_1") (pintype "input"))
      (node (ref "U2") (pin "1") (pinfunction "STAT_1") (pintype "unspecified"))
    )
    (net (code "21") (name "Net-(U4-CONT)") (class "Default")
      (node (ref "C5") (pin "2") (pinfunction "2_2") (pintype "unspecified"))
      (node (ref "U4") (pin "5") (pinfunction "CONT_5") (pintype "unspecified"))
    )
    (net (code "22") (name "Net-(U4-DISCH)") (class "Default")
      (node (ref "C6") (pin "2") (pinfunction "2_2") (pintype "input"))
      (node (ref "R17") (pin "2") (pinfunction "2_2") (pintype "unspecified"))
      (node (ref "U4") (pin "6") (pinfunction "THRES_6") (pintype "unspecified"))
      (node (ref "U4") (pin "7") (pinfunction "DISCH_7") (pintype "unspecified"))
    )
    (net (code "23") (name "Net-(U4-OUT)") (class "Default")
      (node (ref "R18") (pin "2") (pinfunction "2_2") (pintype "input"))
      (node (ref "U4") (pin "3") (pinfunction "OUT_3") (pintype "unspecified"))
    )
    (net (code "24") (name "Net-(USBC1-CC1)") (class "Default")
      (node (ref "R2") (pin "1") (pinfunction "1_1") (pintype "input"))
      (node (ref "USBC1") (pin "A5") (pinfunction "CC1_A5") (pintype "unspecified"))
    )
    (net (code "25") (name "Net-(USBC1-CC2)") (class "Default")
      (node (ref "R1") (pin "2") (pinfunction "2_2") (pintype "input"))
      (node (ref "USBC1") (pin "B5") (pinfunction "CC2_B5") (pintype "unspecified"))
    )
    (net (code "26") (name "PIR Sensor") (class "Default")
      (node (ref "R15") (pin "1") (pinfunction "1_1") (pintype "input"))
    )
    (net (code "27") (name "PIRSensor") (class "Default")
      (node (ref "H10") (pin "2") (pinfunction "2_2") (pintype "unspecified"))
      (node (ref "H5") (pin "1") (pinfunction "1_1") (pintype "unspecified"))
      (node (ref "H7") (pin "2") (pinfunction "2_2") (pintype "unspecified"))
      (node (ref "R13") (pin "2") (pinfunction "2_2") (pintype "input"))
      (node (ref "U3") (pin "4") (pinfunction "REL_4") (pintype "unspecified"))
    )
    (net (code "28") (name "VBat") (class "Default")
      (node (ref "C2") (pin "2") (pinfunction "2_2") (pintype "unspecified"))
      (node (ref "H1") (pin "1") (pinfunction "1_1") (pintype "unspecified"))
      (node (ref "H2") (pin "1") (pinfunction "1_1") (pintype "unspecified"))
      (node (ref "SW1") (pin "1") (pinfunction "1_1") (pintype "unspecified"))
      (node (ref "U2") (pin "3") (pinfunction "VBAT_3") (pintype "unspecified"))
    )
    (net (code "29") (name "Vusb") (class "Default")
      (node (ref "C1") (pin "2") (pinfunction "2_2") (pintype "unspecified"))
      (node (ref "D1") (pin "1") (pinfunction "C_1") (pintype "unspecified"))
      (node (ref "U1") (pin "1") (pinfunction "IN_1") (pintype "unspecified"))
      (node (ref "U1") (pin "3") (pinfunction "EN_3") (pintype "unspecified"))
    )
    (net (code "30") (name "unconnected-(U1-N{slash}C-Pad4)") (class "Default")
      (node (ref "U1") (pin "4") (pinfunction "N/C_4") (pintype "unspecified+no_connect"))
    )
    (net (code "31") (name "unconnected-(USBC1-DN1-PadA7)") (class "Default")
      (node (ref "USBC1") (pin "A7") (pinfunction "DN1_A7") (pintype "unspecified+no_connect"))
    )
    (net (code "32") (name "unconnected-(USBC1-DN2-PadB7)") (class "Default")
      (node (ref "USBC1") (pin "B7") (pinfunction "DN2_B7") (pintype "unspecified+no_connect"))
    )
    (net (code "33") (name "unconnected-(USBC1-DP1-PadA6)") (class "Default")
      (node (ref "USBC1") (pin "A6") (pinfunction "DP1_A6") (pintype "unspecified+no_connect"))
    )
    (net (code "34") (name "unconnected-(USBC1-DP2-PadB6)") (class "Default")
      (node (ref "USBC1") (pin "B6") (pinfunction "DP2_B6") (pintype "unspecified+no_connect"))
    )
    (net (code "35") (name "unconnected-(USBC1-SBU1-PadA8)") (class "Default")
      (node (ref "USBC1") (pin "A8") (pinfunction "SBU1_A8") (pintype "unspecified+no_connect"))
    )
    (net (code "36") (name "unconnected-(USBC1-SBU2-PadB8)") (class "Default")
      (node (ref "USBC1") (pin "B8") (pinfunction "SBU2_B8") (pintype "unspecified+no_connect"))
    )
    (net (code "37") (name "unconnected-(USBC1-VBUS-PadA9)") (class "Default")
      (node (ref "USBC1") (pin "A9") (pinfunction "VBUS_A9") (pintype "unspecified+no_connect"))
    )
  )
)
